# PCEmon_PLUS_rev_C.net
KiCad netlist of a schematic drawn in EAGLE
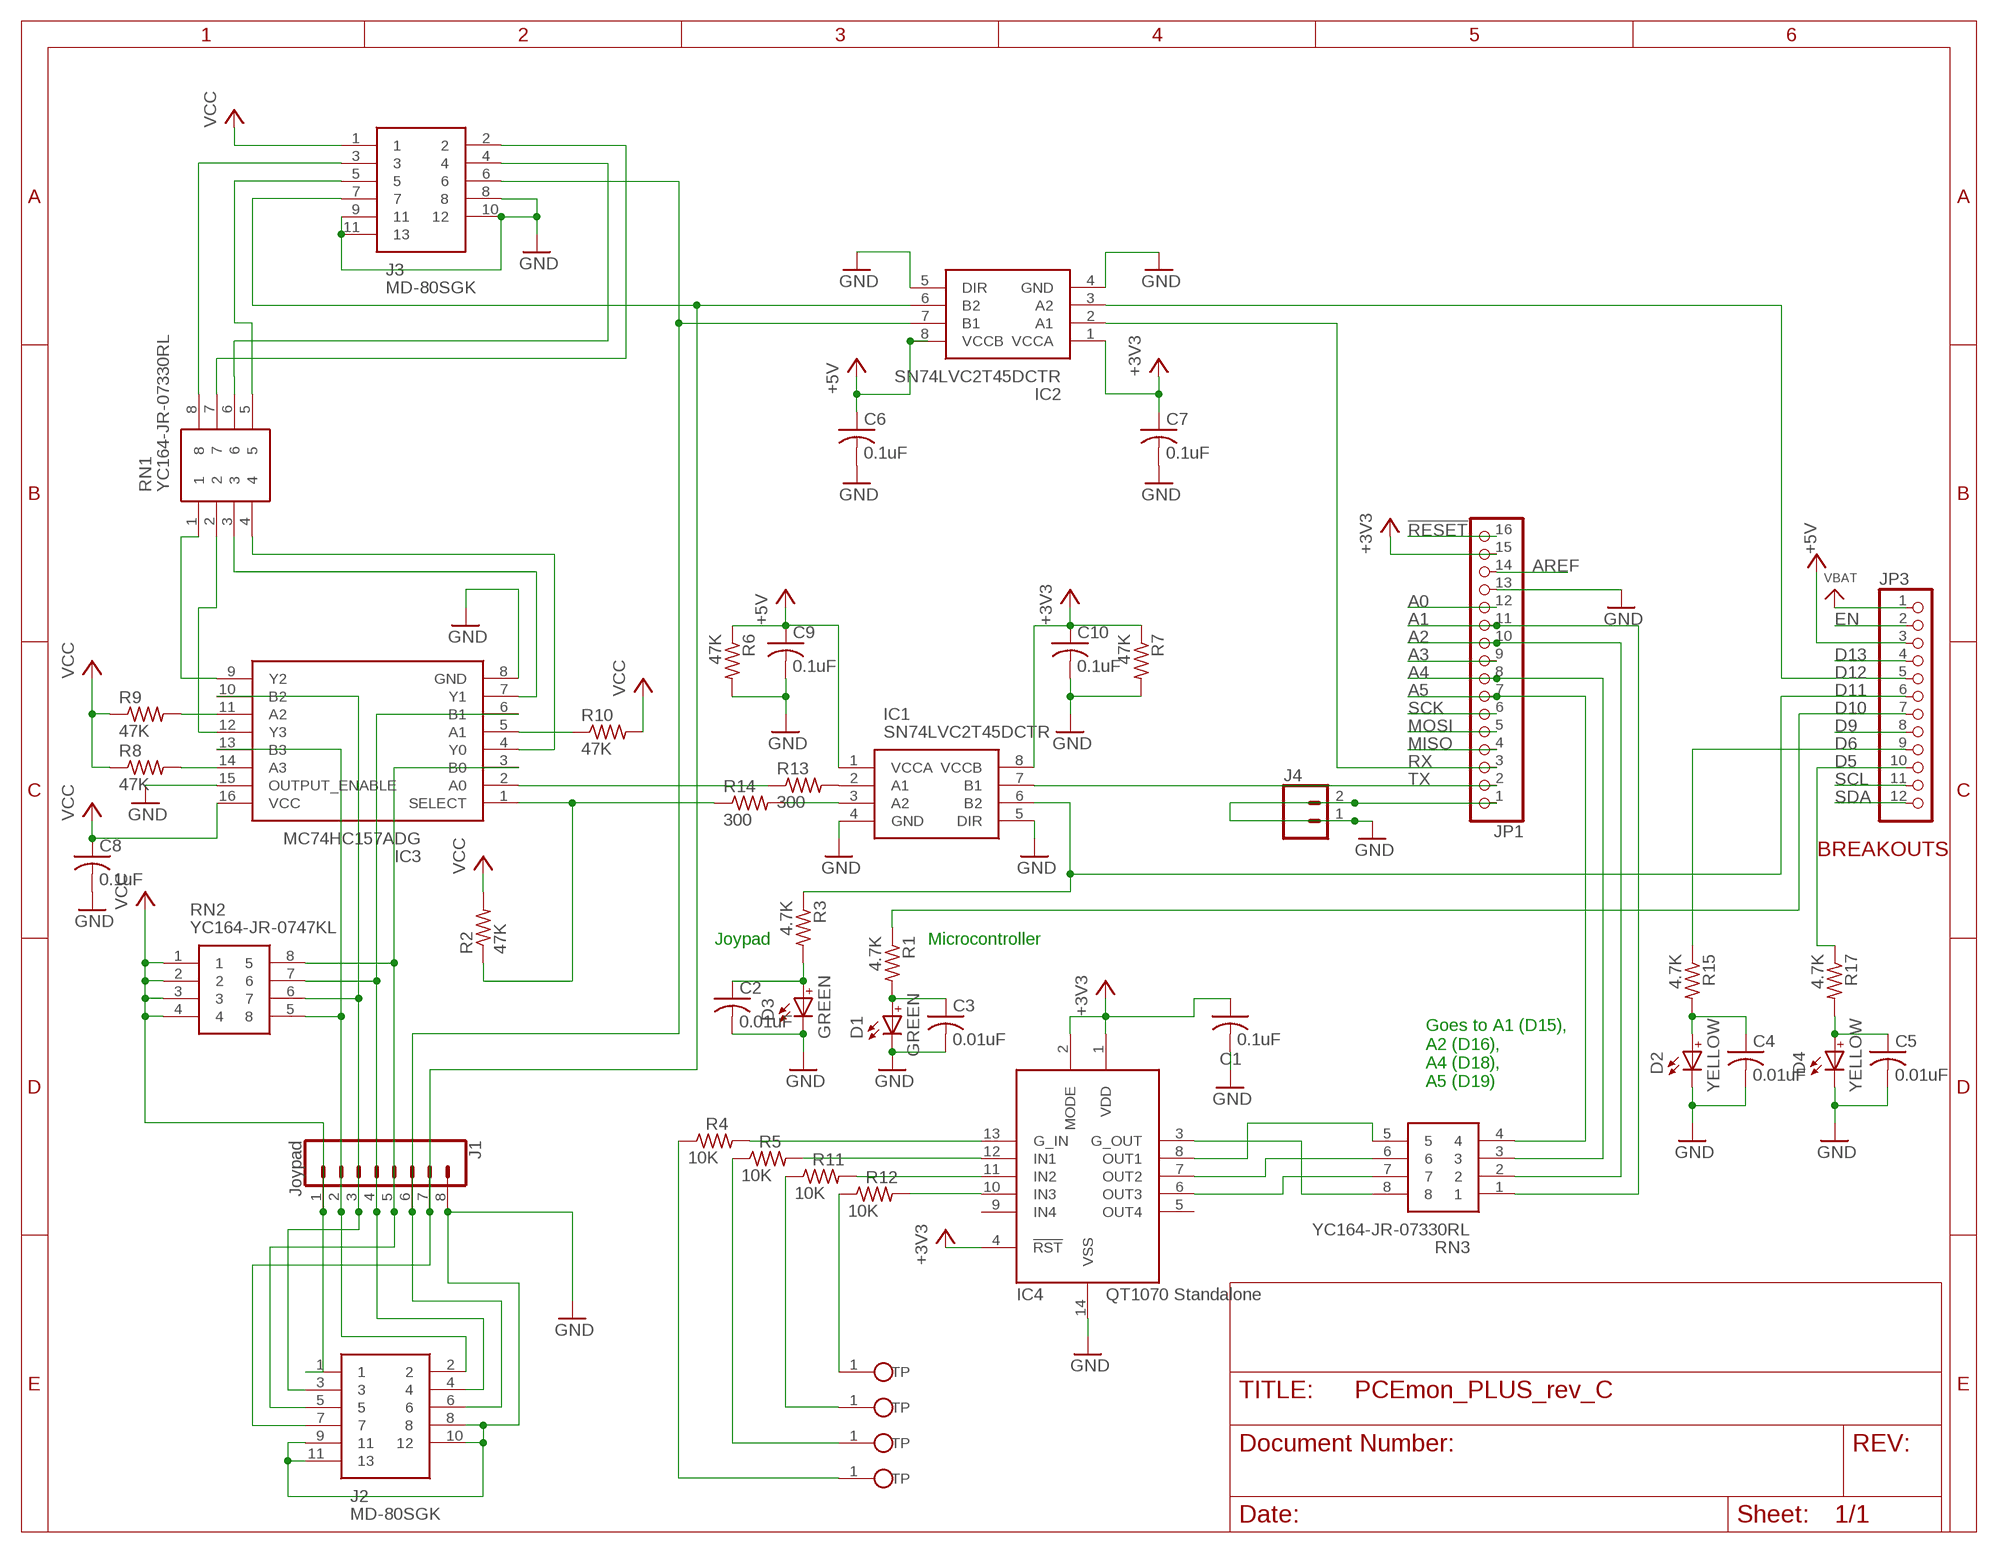
[diagram p0: schematic, sheet 1]

(export (version "E")
  (design (tool "Eeschema 10.0.6"))
  (components
    (comp (ref "C1")
      (value "0.1uF")
      (footprint "eagle-import:C0603")
      (libsource (lib "eagle-import") (part "C-USC0603"))
    )
    (comp (ref "C2")
      (value "0.01uF")
      (footprint "eagle-import:C0603")
      (libsource (lib "eagle-import") (part "C-USC0603"))
    )
    (comp (ref "C3")
      (value "0.01uF")
      (footprint "eagle-import:C0603")
      (libsource (lib "eagle-import") (part "C-USC0603"))
    )
    (comp (ref "C4")
      (value "0.01uF")
      (footprint "eagle-import:C0603")
      (libsource (lib "eagle-import") (part "C-USC0603"))
    )
    (comp (ref "C5")
      (value "0.01uF")
      (footprint "eagle-import:C0603")
      (libsource (lib "eagle-import") (part "C-USC0603"))
    )
    (comp (ref "C6")
      (value "0.1uF")
      (footprint "eagle-import:C0603")
      (libsource (lib "eagle-import") (part "C-USC0603"))
    )
    (comp (ref "C7")
      (value "0.1uF")
      (footprint "eagle-import:C0603")
      (libsource (lib "eagle-import") (part "C-USC0603"))
    )
    (comp (ref "C8")
      (value "0.1uF")
      (footprint "eagle-import:C0603")
      (libsource (lib "eagle-import") (part "C-USC0603"))
    )
    (comp (ref "C9")
      (value "0.1uF")
      (footprint "eagle-import:C0603")
      (libsource (lib "eagle-import") (part "C-USC0603"))
    )
    (comp (ref "C10")
      (value "0.1uF")
      (footprint "eagle-import:C0603")
      (libsource (lib "eagle-import") (part "C-USC0603"))
    )
    (comp (ref "D1")
      (value "GREEN")
      (footprint "eagle-import:WL-SMCC_0603_R_Y_V")
      (libsource (lib "eagle-import") (part "WL-SMCC_0603_R/V/Y_150060RS73220"))
    )
    (comp (ref "D2")
      (value "YELLOW")
      (footprint "eagle-import:WL-SMCC_0603_R_Y_V")
      (libsource (lib "eagle-import") (part "WL-SMCC_0603_R/V/Y_150060RS73220"))
    )
    (comp (ref "D3")
      (value "GREEN")
      (footprint "eagle-import:WL-SMCC_0603_R_Y_V")
      (libsource (lib "eagle-import") (part "WL-SMCC_0603_R/V/Y_150060RS73220"))
    )
    (comp (ref "D4")
      (value "YELLOW")
      (footprint "eagle-import:WL-SMCC_0603_R_Y_V")
      (libsource (lib "eagle-import") (part "WL-SMCC_0603_R/V/Y_150060RS73220"))
    )
    (comp (ref "IC1")
      (value "SN74LVC2T45DCTR")
      (footprint "eagle-import:SOP65P400X130-8N")
      (fields
        (field (name "MOUSER_PART_NUMBER") "595-SN74LVC2T45DCTR")
        (field (name "RS_PART_NUMBER") "9213022")
      )
      (libsource (lib "eagle-import") (part "SN74LVC2T45DCTR"))
    )
    (comp (ref "IC2")
      (value "SN74LVC2T45DCTR")
      (footprint "eagle-import:SOP65P400X130-8N")
      (fields
        (field (name "MOUSER_PART_NUMBER") "595-SN74LVC2T45DCTR")
        (field (name "RS_PART_NUMBER") "9213022")
      )
      (libsource (lib "eagle-import") (part "SN74LVC2T45DCTR"))
    )
    (comp (ref "IC3")
      (value "MC74HC157ADG")
      (footprint "eagle-import:SOIC127P600X175-16N")
      (fields
        (field (name "MOUSER_PART_NUMBER") "863-MC74HC157ADG")
        (field (name "RS_PART_NUMBER") "8061422P")
      )
      (libsource (lib "eagle-import") (part "MC74HC157ADG"))
    )
    (comp (ref "IC4")
      (value "AT42QT1070-SSU")
      (footprint "eagle-import:SO14")
      (libsource (lib "eagle-import") (part "AT42QT1070-SSU"))
    )
    (comp (ref "J1")
      (value "Joypad")
      (footprint "eagle-import:1X08")
      (libsource (lib "eagle-import") (part "CONN_08{dblquote}"))
    )
    (comp (ref "J2")
      (value "MD-80SGK")
      (footprint "eagle-import:MD80SGK")
      (fields (field (name "MOUSER_PART_NUMBER") "490-MD-80SGK"))
      (libsource (lib "eagle-import") (part "MD-80SGK"))
    )
    (comp (ref "J3")
      (value "MD-80SGK")
      (footprint "eagle-import:MD80SGK")
      (fields (field (name "MOUSER_PART_NUMBER") "490-MD-80SGK"))
      (libsource (lib "eagle-import") (part "MD-80SGK"))
    )
    (comp (ref "J4")
      (value "CONN_021X02_NO_SILK")
      (footprint "eagle-import:1X02_NO_SILK")
      (libsource (lib "eagle-import") (part "CONN_021X02_NO_SILK"))
    )
    (comp (ref "JP1")
      (value "HEADER-1X16ROUND")
      (footprint "eagle-import:1X16_ROUND")
      (libsource (lib "eagle-import") (part "HEADER-1X16ROUND"))
    )
    (comp (ref "JP3")
      (value "HEADER-1X12")
      (footprint "eagle-import:1X12_ROUND")
      (libsource (lib "eagle-import") (part "HEADER-1X12"))
    )
    (comp (ref "P1")
      (value "JOYPAD")
      (footprint "eagle-import:TOUCH-350X500")
      (libsource (lib "eagle-import") (part "TOUCHPAD-350X500"))
    )
    (comp (ref "P2")
      (value "COMPUTER")
      (footprint "eagle-import:TOUCH-350X500")
      (libsource (lib "eagle-import") (part "TOUCHPAD-350X500"))
    )
    (comp (ref "P3")
      (value "Original Mode")
      (footprint "eagle-import:TOUCH-350X500")
      (libsource (lib "eagle-import") (part "TOUCHPAD-350X500"))
    )
    (comp (ref "P4")
      (value "PLUS Mode")
      (footprint "eagle-import:TOUCH-350X500")
      (libsource (lib "eagle-import") (part "TOUCHPAD-350X500"))
    )
    (comp (ref "R1")
      (value "4.7K")
      (footprint "eagle-import:R0603")
      (libsource (lib "eagle-import") (part "R-US_R0603"))
    )
    (comp (ref "R2")
      (value "47K")
      (footprint "eagle-import:R0603")
      (libsource (lib "eagle-import") (part "R-US_R0603"))
    )
    (comp (ref "R3")
      (value "4.7K")
      (footprint "eagle-import:R0603")
      (libsource (lib "eagle-import") (part "R-US_R0603"))
    )
    (comp (ref "R4")
      (value "10K")
      (footprint "eagle-import:R0603")
      (libsource (lib "eagle-import") (part "R-US_R0603"))
    )
    (comp (ref "R5")
      (value "10K")
      (footprint "eagle-import:R0603")
      (libsource (lib "eagle-import") (part "R-US_R0603"))
    )
    (comp (ref "R6")
      (value "47K")
      (footprint "eagle-import:R0603")
      (libsource (lib "eagle-import") (part "R-US_R0603"))
    )
    (comp (ref "R7")
      (value "47K")
      (footprint "eagle-import:R0603")
      (libsource (lib "eagle-import") (part "R-US_R0603"))
    )
    (comp (ref "R8")
      (value "47K")
      (footprint "eagle-import:R0603")
      (libsource (lib "eagle-import") (part "R-US_R0603"))
    )
    (comp (ref "R9")
      (value "47K")
      (footprint "eagle-import:R0603")
      (libsource (lib "eagle-import") (part "R-US_R0603"))
    )
    (comp (ref "R10")
      (value "47K")
      (footprint "eagle-import:R0603")
      (libsource (lib "eagle-import") (part "R-US_R0603"))
    )
    (comp (ref "R11")
      (value "10K")
      (footprint "eagle-import:R0603")
      (libsource (lib "eagle-import") (part "R-US_R0603"))
    )
    (comp (ref "R12")
      (value "10K")
      (footprint "eagle-import:R0603")
      (libsource (lib "eagle-import") (part "R-US_R0603"))
    )
    (comp (ref "R13")
      (value "300")
      (footprint "eagle-import:R0603")
      (libsource (lib "eagle-import") (part "R-US_R0603"))
    )
    (comp (ref "R14")
      (value "300")
      (footprint "eagle-import:R0603")
      (libsource (lib "eagle-import") (part "R-US_R0603"))
    )
    (comp (ref "R15")
      (value "4.7K")
      (footprint "eagle-import:R0603")
      (libsource (lib "eagle-import") (part "R-US_R0603"))
    )
    (comp (ref "R17")
      (value "4.7K")
      (footprint "eagle-import:R0603")
      (libsource (lib "eagle-import") (part "R-US_R0603"))
    )
    (comp (ref "RN1")
      (value "YC164-JR-07330RL")
      (footprint "eagle-import:YC164JR07220RL")
      (fields (field (name "MOUSER_PART_NUMBER") "603-YC164-JR-07330RL"))
      (libsource (lib "eagle-import") (part "YC164-JR-07330RL"))
    )
    (comp (ref "RN2")
      (value "YC164-JR-0747KL")
      (footprint "eagle-import:YC164JR07220RL")
      (fields (field (name "MOUSER_PART_NUMBER") "603-YC164-JR-0747KL"))
      (libsource (lib "eagle-import") (part "YC164-JR-0747KL"))
    )
    (comp (ref "RN3")
      (value "YC164-JR-07330RL")
      (footprint "eagle-import:YC164JR07220RL")
      (fields (field (name "MOUSER_PART_NUMBER") "603-YC164-JR-07330RL"))
      (libsource (lib "eagle-import") (part "YC164-JR-07330RL"))
    )
  )
  (nets
    (net (code "1") (name "+3V3") (class "Default")
      (node (ref "C1") (pin "1") (pinfunction "1_1") (pintype "passive"))
      (node (ref "C10") (pin "1") (pinfunction "1_1") (pintype "passive"))
      (node (ref "C7") (pin "1") (pinfunction "1_1") (pintype "passive"))
      (node (ref "IC1") (pin "8") (pinfunction "VCCB_8") (pintype "power_in"))
      (node (ref "IC2") (pin "1") (pinfunction "VCCA_1") (pintype "power_in"))
      (node (ref "IC4") (pin "1") (pinfunction "VDD_1") (pintype "power_in"))
      (node (ref "IC4") (pin "2") (pinfunction "MODE_2") (pintype "input"))
      (node (ref "IC4") (pin "4") (pinfunction "~{RST}_4") (pintype "input"))
      (node (ref "JP1") (pin "15") (pinfunction "15_15") (pintype "passive"))
      (node (ref "R7") (pin "1") (pinfunction "1_1") (pintype "passive"))
    )
    (net (code "2") (name "+5V") (class "Default")
      (node (ref "C6") (pin "1") (pinfunction "1_1") (pintype "passive"))
      (node (ref "C9") (pin "1") (pinfunction "1_1") (pintype "passive"))
      (node (ref "IC1") (pin "1") (pinfunction "VCCA_1") (pintype "power_in"))
      (node (ref "IC2") (pin "8") (pinfunction "VCCB_8") (pintype "power_in"))
      (node (ref "JP3") (pin "3") (pinfunction "3_3") (pintype "passive"))
      (node (ref "R6") (pin "1") (pinfunction "1_1") (pintype "passive"))
    )
    (net (code "3") (name "/A0") (class "Default")
      (node (ref "JP1") (pin "12") (pinfunction "12_12") (pintype "passive"))
    )
    (net (code "4") (name "/A1") (class "Default")
      (node (ref "JP1") (pin "11") (pinfunction "11_11") (pintype "passive"))
      (node (ref "RN3") (pin "1") (pinfunction "1_1") (pintype "bidirectional"))
    )
    (net (code "5") (name "/A2") (class "Default")
      (node (ref "JP1") (pin "10") (pinfunction "10_10") (pintype "passive"))
      (node (ref "RN3") (pin "2") (pinfunction "2_2") (pintype "bidirectional"))
    )
    (net (code "6") (name "/A3") (class "Default")
      (node (ref "JP1") (pin "9") (pinfunction "9_9") (pintype "passive"))
    )
    (net (code "7") (name "/A4") (class "Default")
      (node (ref "JP1") (pin "8") (pinfunction "8_8") (pintype "passive"))
      (node (ref "RN3") (pin "3") (pinfunction "3_3") (pintype "bidirectional"))
    )
    (net (code "8") (name "/A5") (class "Default")
      (node (ref "JP1") (pin "7") (pinfunction "7_7") (pintype "passive"))
      (node (ref "RN3") (pin "4") (pinfunction "4_4") (pintype "bidirectional"))
    )
    (net (code "9") (name "/AREF") (class "Default")
      (node (ref "JP1") (pin "14") (pinfunction "14_14") (pintype "passive"))
    )
    (net (code "10") (name "/D5") (class "Default")
      (node (ref "JP3") (pin "10") (pinfunction "10_10") (pintype "passive"))
      (node (ref "R17") (pin "1") (pinfunction "1_1") (pintype "passive"))
    )
    (net (code "11") (name "/D6") (class "Default")
      (node (ref "JP3") (pin "9") (pinfunction "9_9") (pintype "passive"))
      (node (ref "R15") (pin "1") (pinfunction "1_1") (pintype "passive"))
    )
    (net (code "12") (name "/D9") (class "Default")
      (node (ref "JP3") (pin "8") (pinfunction "8_8") (pintype "passive"))
    )
    (net (code "13") (name "/D10") (class "Default")
      (node (ref "JP3") (pin "7") (pinfunction "7_7") (pintype "passive"))
      (node (ref "R1") (pin "1") (pinfunction "1_1") (pintype "passive"))
    )
    (net (code "14") (name "/D11") (class "Default")
      (node (ref "IC1") (pin "6") (pinfunction "B2_6") (pintype "bidirectional"))
      (node (ref "JP3") (pin "6") (pinfunction "6_6") (pintype "passive"))
      (node (ref "R3") (pin "1") (pinfunction "1_1") (pintype "passive"))
    )
    (net (code "15") (name "/D12") (class "Default")
      (node (ref "IC2") (pin "3") (pinfunction "A2_3") (pintype "bidirectional"))
      (node (ref "JP3") (pin "5") (pinfunction "5_5") (pintype "passive"))
    )
    (net (code "16") (name "/D13") (class "Default")
      (node (ref "JP3") (pin "4") (pinfunction "4_4") (pintype "passive"))
    )
    (net (code "17") (name "/EN") (class "Default")
      (node (ref "JP3") (pin "2") (pinfunction "2_2") (pintype "passive"))
    )
    (net (code "18") (name "/MISO") (class "Default")
      (node (ref "JP1") (pin "4") (pinfunction "4_4") (pintype "passive"))
    )
    (net (code "19") (name "/MOSI") (class "Default")
      (node (ref "JP1") (pin "5") (pinfunction "5_5") (pintype "passive"))
    )
    (net (code "20") (name "/RX") (class "Default")
      (node (ref "IC2") (pin "2") (pinfunction "A1_2") (pintype "bidirectional"))
      (node (ref "JP1") (pin "3") (pinfunction "3_3") (pintype "passive"))
    )
    (net (code "21") (name "/SCK") (class "Default")
      (node (ref "JP1") (pin "6") (pinfunction "6_6") (pintype "passive"))
    )
    (net (code "22") (name "/SCL") (class "Default")
      (node (ref "JP3") (pin "11") (pinfunction "11_11") (pintype "passive"))
    )
    (net (code "23") (name "/SDA") (class "Default")
      (node (ref "JP3") (pin "12") (pinfunction "12_12") (pintype "passive"))
    )
    (net (code "24") (name "/TX") (class "Default")
      (node (ref "IC1") (pin "7") (pinfunction "B1_7") (pintype "bidirectional"))
      (node (ref "JP1") (pin "2") (pinfunction "2_2") (pintype "passive"))
    )
    (net (code "25") (name "/~{RESET}") (class "Default")
      (node (ref "JP1") (pin "16") (pinfunction "16_16") (pintype "passive"))
    )
    (net (code "26") (name "GND") (class "Default")
      (node (ref "C1") (pin "2") (pinfunction "2_2") (pintype "passive"))
      (node (ref "C10") (pin "2") (pinfunction "2_2") (pintype "passive"))
      (node (ref "C2") (pin "2") (pinfunction "2_2") (pintype "passive"))
      (node (ref "C3") (pin "2") (pinfunction "2_2") (pintype "passive"))
      (node (ref "C4") (pin "2") (pinfunction "2_2") (pintype "passive"))
      (node (ref "C5") (pin "2") (pinfunction "2_2") (pintype "passive"))
      (node (ref "C6") (pin "2") (pinfunction "2_2") (pintype "passive"))
      (node (ref "C7") (pin "2") (pinfunction "2_2") (pintype "passive"))
      (node (ref "C8") (pin "2") (pinfunction "2_2") (pintype "passive"))
      (node (ref "C9") (pin "2") (pinfunction "2_2") (pintype "passive"))
      (node (ref "D1") (pin "1") (pinfunction "C_1") (pintype "passive"))
      (node (ref "D2") (pin "1") (pinfunction "C_1") (pintype "passive"))
      (node (ref "D3") (pin "1") (pinfunction "C_1") (pintype "passive"))
      (node (ref "D4") (pin "1") (pinfunction "C_1") (pintype "passive"))
      (node (ref "IC1") (pin "4") (pinfunction "GND_4") (pintype "power_in"))
      (node (ref "IC1") (pin "5") (pinfunction "DIR_5") (pintype "bidirectional"))
      (node (ref "IC2") (pin "4") (pinfunction "GND_4") (pintype "power_in"))
      (node (ref "IC2") (pin "5") (pinfunction "DIR_5") (pintype "bidirectional"))
      (node (ref "IC3") (pin "15") (pinfunction "OUTPUT_ENABLE_15") (pintype "input"))
      (node (ref "IC3") (pin "8") (pinfunction "GND_8") (pintype "power_in"))
      (node (ref "IC4") (pin "14") (pinfunction "VSS_14") (pintype "power_in"))
      (node (ref "J1") (pin "8") (pinfunction "8_8") (pintype "passive"))
      (node (ref "J2") (pin "10") (pinfunction "12_10") (pintype "bidirectional"))
      (node (ref "J2") (pin "11") (pinfunction "13_11") (pintype "bidirectional"))
      (node (ref "J2") (pin "8") (pinfunction "8_8") (pintype "bidirectional"))
      (node (ref "J2") (pin "9") (pinfunction "11_9") (pintype "bidirectional"))
      (node (ref "J3") (pin "10") (pinfunction "12_10") (pintype "bidirectional"))
      (node (ref "J3") (pin "11") (pinfunction "13_11") (pintype "bidirectional"))
      (node (ref "J3") (pin "8") (pinfunction "8_8") (pintype "bidirectional"))
      (node (ref "J3") (pin "9") (pinfunction "11_9") (pintype "bidirectional"))
      (node (ref "J4") (pin "1") (pinfunction "1_1") (pintype "passive"))
      (node (ref "J4") (pin "2") (pinfunction "2_2") (pintype "passive"))
      (node (ref "JP1") (pin "1") (pinfunction "1_1") (pintype "passive"))
      (node (ref "JP1") (pin "13") (pinfunction "13_13") (pintype "passive"))
      (node (ref "R6") (pin "2") (pinfunction "2_2") (pintype "passive"))
      (node (ref "R7") (pin "2") (pinfunction "2_2") (pintype "passive"))
    )
    (net (code "27") (name "Net-(D1-A)") (class "Default")
      (node (ref "C3") (pin "1") (pinfunction "1_1") (pintype "passive"))
      (node (ref "D1") (pin "2") (pinfunction "A_2") (pintype "passive"))
      (node (ref "R1") (pin "2") (pinfunction "2_2") (pintype "passive"))
    )
    (net (code "28") (name "Net-(D2-A)") (class "Default")
      (node (ref "C4") (pin "1") (pinfunction "1_1") (pintype "passive"))
      (node (ref "D2") (pin "2") (pinfunction "A_2") (pintype "passive"))
      (node (ref "R15") (pin "2") (pinfunction "2_2") (pintype "passive"))
    )
    (net (code "29") (name "Net-(D3-A)") (class "Default")
      (node (ref "C2") (pin "1") (pinfunction "1_1") (pintype "passive"))
      (node (ref "D3") (pin "2") (pinfunction "A_2") (pintype "passive"))
      (node (ref "R3") (pin "2") (pinfunction "2_2") (pintype "passive"))
    )
    (net (code "30") (name "Net-(D4-A)") (class "Default")
      (node (ref "C5") (pin "1") (pinfunction "1_1") (pintype "passive"))
      (node (ref "D4") (pin "2") (pinfunction "A_2") (pintype "passive"))
      (node (ref "R17") (pin "2") (pinfunction "2_2") (pintype "passive"))
    )
    (net (code "31") (name "Net-(IC1-A1)") (class "Default")
      (node (ref "IC1") (pin "2") (pinfunction "A1_2") (pintype "bidirectional"))
      (node (ref "R13") (pin "2") (pinfunction "2_2") (pintype "passive"))
    )
    (net (code "32") (name "Net-(IC1-A2)") (class "Default")
      (node (ref "IC1") (pin "3") (pinfunction "A2_3") (pintype "bidirectional"))
      (node (ref "R14") (pin "2") (pinfunction "2_2") (pintype "passive"))
    )
    (net (code "33") (name "Net-(IC2-B1)") (class "Default")
      (node (ref "IC2") (pin "7") (pinfunction "B1_7") (pintype "bidirectional"))
      (node (ref "J1") (pin "6") (pinfunction "6_6") (pintype "passive"))
      (node (ref "J2") (pin "6") (pinfunction "6_6") (pintype "bidirectional"))
      (node (ref "J3") (pin "6") (pinfunction "6_6") (pintype "bidirectional"))
    )
    (net (code "34") (name "Net-(IC2-B2)") (class "Default")
      (node (ref "IC2") (pin "6") (pinfunction "B2_6") (pintype "bidirectional"))
      (node (ref "J1") (pin "7") (pinfunction "7_7") (pintype "passive"))
      (node (ref "J2") (pin "7") (pinfunction "7_7") (pintype "bidirectional"))
      (node (ref "J3") (pin "7") (pinfunction "7_7") (pintype "bidirectional"))
    )
    (net (code "35") (name "Net-(IC3-A0)") (class "Default")
      (node (ref "IC3") (pin "2") (pinfunction "A0_2") (pintype "input"))
      (node (ref "R13") (pin "1") (pinfunction "1_1") (pintype "passive"))
    )
    (net (code "36") (name "Net-(IC3-A1)") (class "Default")
      (node (ref "IC3") (pin "5") (pinfunction "A1_5") (pintype "input"))
      (node (ref "R10") (pin "1") (pinfunction "1_1") (pintype "passive"))
    )
    (net (code "37") (name "Net-(IC3-A2)") (class "Default")
      (node (ref "IC3") (pin "11") (pinfunction "A2_11") (pintype "input"))
      (node (ref "R9") (pin "2") (pinfunction "2_2") (pintype "passive"))
    )
    (net (code "38") (name "Net-(IC3-A3)") (class "Default")
      (node (ref "IC3") (pin "14") (pinfunction "A3_14") (pintype "input"))
      (node (ref "R8") (pin "2") (pinfunction "2_2") (pintype "passive"))
    )
    (net (code "39") (name "Net-(IC3-B0)") (class "Default")
      (node (ref "IC3") (pin "3") (pinfunction "B0_3") (pintype "input"))
      (node (ref "J1") (pin "5") (pinfunction "5_5") (pintype "passive"))
      (node (ref "J2") (pin "5") (pinfunction "5_5") (pintype "bidirectional"))
      (node (ref "RN2") (pin "8") (pinfunction "5_8") (pintype "bidirectional"))
    )
    (net (code "40") (name "Net-(IC3-B1)") (class "Default")
      (node (ref "IC3") (pin "6") (pinfunction "B1_6") (pintype "input"))
      (node (ref "J1") (pin "4") (pinfunction "4_4") (pintype "passive"))
      (node (ref "J2") (pin "4") (pinfunction "4_4") (pintype "bidirectional"))
      (node (ref "RN2") (pin "7") (pinfunction "6_7") (pintype "bidirectional"))
    )
    (net (code "41") (name "Net-(IC3-B2)") (class "Default")
      (node (ref "IC3") (pin "10") (pinfunction "B2_10") (pintype "input"))
      (node (ref "J1") (pin "3") (pinfunction "3_3") (pintype "passive"))
      (node (ref "J2") (pin "3") (pinfunction "3_3") (pintype "bidirectional"))
      (node (ref "RN2") (pin "6") (pinfunction "7_6") (pintype "bidirectional"))
    )
    (net (code "42") (name "Net-(IC3-B3)") (class "Default")
      (node (ref "IC3") (pin "13") (pinfunction "B3_13") (pintype "input"))
      (node (ref "J1") (pin "2") (pinfunction "2_2") (pintype "passive"))
      (node (ref "J2") (pin "2") (pinfunction "2_2") (pintype "bidirectional"))
      (node (ref "RN2") (pin "5") (pinfunction "8_5") (pintype "bidirectional"))
    )
    (net (code "43") (name "Net-(IC3-SELECT)") (class "Default")
      (node (ref "IC3") (pin "1") (pinfunction "SELECT_1") (pintype "input"))
      (node (ref "R14") (pin "1") (pinfunction "1_1") (pintype "passive"))
      (node (ref "R2") (pin "1") (pinfunction "1_1") (pintype "passive"))
    )
    (net (code "44") (name "Net-(IC3-Y0)") (class "Default")
      (node (ref "IC3") (pin "4") (pinfunction "Y0_4") (pintype "output"))
      (node (ref "RN1") (pin "4") (pinfunction "4_4") (pintype "bidirectional"))
    )
    (net (code "45") (name "Net-(IC3-Y1)") (class "Default")
      (node (ref "IC3") (pin "7") (pinfunction "Y1_7") (pintype "output"))
      (node (ref "RN1") (pin "3") (pinfunction "3_3") (pintype "bidirectional"))
    )
    (net (code "46") (name "Net-(IC3-Y2)") (class "Default")
      (node (ref "IC3") (pin "9") (pinfunction "Y2_9") (pintype "output"))
      (node (ref "RN1") (pin "1") (pinfunction "1_1") (pintype "bidirectional"))
    )
    (net (code "47") (name "Net-(IC3-Y3)") (class "Default")
      (node (ref "IC3") (pin "12") (pinfunction "Y3_12") (pintype "output"))
      (node (ref "RN1") (pin "2") (pinfunction "2_2") (pintype "bidirectional"))
    )
    (net (code "48") (name "Net-(IC4-G_IN)") (class "Default")
      (node (ref "IC4") (pin "13") (pinfunction "G_IN_13") (pintype "input"))
      (node (ref "R4") (pin "2") (pinfunction "2_2") (pintype "passive"))
    )
    (net (code "49") (name "Net-(IC4-G_OUT)") (class "Default")
      (node (ref "IC4") (pin "3") (pinfunction "G_OUT_3") (pintype "open_collector"))
      (node (ref "RN3") (pin "8") (pinfunction "8_8") (pintype "bidirectional"))
    )
    (net (code "50") (name "Net-(IC4-IN1)") (class "Default")
      (node (ref "IC4") (pin "12") (pinfunction "IN1_12") (pintype "input"))
      (node (ref "R5") (pin "2") (pinfunction "2_2") (pintype "passive"))
    )
    (net (code "51") (name "Net-(IC4-IN2)") (class "Default")
      (node (ref "IC4") (pin "11") (pinfunction "IN2_11") (pintype "input"))
      (node (ref "R11") (pin "2") (pinfunction "2_2") (pintype "passive"))
    )
    (net (code "52") (name "Net-(IC4-IN3)") (class "Default")
      (node (ref "IC4") (pin "10") (pinfunction "IN3_10") (pintype "input"))
      (node (ref "R12") (pin "2") (pinfunction "2_2") (pintype "passive"))
    )
    (net (code "53") (name "Net-(IC4-OUT1)") (class "Default")
      (node (ref "IC4") (pin "8") (pinfunction "OUT1_8") (pintype "open_collector"))
      (node (ref "RN3") (pin "5") (pinfunction "5_5") (pintype "bidirectional"))
    )
    (net (code "54") (name "Net-(IC4-OUT2)") (class "Default")
      (node (ref "IC4") (pin "7") (pinfunction "OUT2_7") (pintype "open_collector"))
      (node (ref "RN3") (pin "6") (pinfunction "6_6") (pintype "bidirectional"))
    )
    (net (code "55") (name "Net-(IC4-OUT3)") (class "Default")
      (node (ref "IC4") (pin "6") (pinfunction "OUT3_6") (pintype "open_collector"))
      (node (ref "RN3") (pin "7") (pinfunction "7_7") (pintype "bidirectional"))
    )
    (net (code "56") (name "Net-(J3-Pad2)") (class "Default")
      (node (ref "J3") (pin "2") (pinfunction "2_2") (pintype "bidirectional"))
      (node (ref "RN1") (pin "7") (pinfunction "7_7") (pintype "bidirectional"))
    )
    (net (code "57") (name "Net-(J3-Pad3)") (class "Default")
      (node (ref "J3") (pin "3") (pinfunction "3_3") (pintype "bidirectional"))
      (node (ref "RN1") (pin "8") (pinfunction "8_8") (pintype "bidirectional"))
    )
    (net (code "58") (name "Net-(J3-Pad4)") (class "Default")
      (node (ref "J3") (pin "4") (pinfunction "4_4") (pintype "bidirectional"))
      (node (ref "RN1") (pin "6") (pinfunction "6_6") (pintype "bidirectional"))
    )
    (net (code "59") (name "Net-(J3-Pad5)") (class "Default")
      (node (ref "J3") (pin "5") (pinfunction "5_5") (pintype "bidirectional"))
      (node (ref "RN1") (pin "5") (pinfunction "5_5") (pintype "bidirectional"))
    )
    (net (code "60") (name "Net-(P1-TP)") (class "Default")
      (node (ref "P1") (pin "1") (pinfunction "TP_1") (pintype "bidirectional"))
      (node (ref "R12") (pin "1") (pinfunction "1_1") (pintype "passive"))
    )
    (net (code "61") (name "Net-(P2-TP)") (class "Default")
      (node (ref "P2") (pin "1") (pinfunction "TP_1") (pintype "bidirectional"))
      (node (ref "R11") (pin "1") (pinfunction "1_1") (pintype "passive"))
    )
    (net (code "62") (name "Net-(P3-TP)") (class "Default")
      (node (ref "P3") (pin "1") (pinfunction "TP_1") (pintype "bidirectional"))
      (node (ref "R5") (pin "1") (pinfunction "1_1") (pintype "passive"))
    )
    (net (code "63") (name "Net-(P4-TP)") (class "Default")
      (node (ref "P4") (pin "1") (pinfunction "TP_1") (pintype "bidirectional"))
      (node (ref "R4") (pin "1") (pinfunction "1_1") (pintype "passive"))
    )
    (net (code "64") (name "VBAT") (class "Default")
      (node (ref "JP3") (pin "1") (pinfunction "1_1") (pintype "passive"))
    )
    (net (code "65") (name "VCC") (class "Default")
      (node (ref "C8") (pin "1") (pinfunction "1_1") (pintype "passive"))
      (node (ref "IC3") (pin "16") (pinfunction "VCC_16") (pintype "power_in"))
      (node (ref "J1") (pin "1") (pinfunction "1_1") (pintype "passive"))
      (node (ref "J2") (pin "1") (pinfunction "1_1") (pintype "bidirectional"))
      (node (ref "J3") (pin "1") (pinfunction "1_1") (pintype "bidirectional"))
      (node (ref "R10") (pin "2") (pinfunction "2_2") (pintype "passive"))
      (node (ref "R2") (pin "2") (pinfunction "2_2") (pintype "passive"))
      (node (ref "R8") (pin "1") (pinfunction "1_1") (pintype "passive"))
      (node (ref "R9") (pin "1") (pinfunction "1_1") (pintype "passive"))
      (node (ref "RN2") (pin "1") (pinfunction "1_1") (pintype "bidirectional"))
      (node (ref "RN2") (pin "2") (pinfunction "2_2") (pintype "bidirectional"))
      (node (ref "RN2") (pin "3") (pinfunction "3_3") (pintype "bidirectional"))
      (node (ref "RN2") (pin "4") (pinfunction "4_4") (pintype "bidirectional"))
    )
    (net (code "66") (name "unconnected-(IC4-IN4-Pad9)") (class "Default")
      (node (ref "IC4") (pin "9") (pinfunction "IN4_9") (pintype "input"))
    )
    (net (code "67") (name "unconnected-(IC4-OUT4-Pad5)") (class "Default")
      (node (ref "IC4") (pin "5") (pinfunction "OUT4_5") (pintype "open_collector"))
    )
  )
)
